# ProPrj_gpsdo-Phil1_2025-08-17.net
KiCad netlist of a schematic drawn in EasyEDA Pro
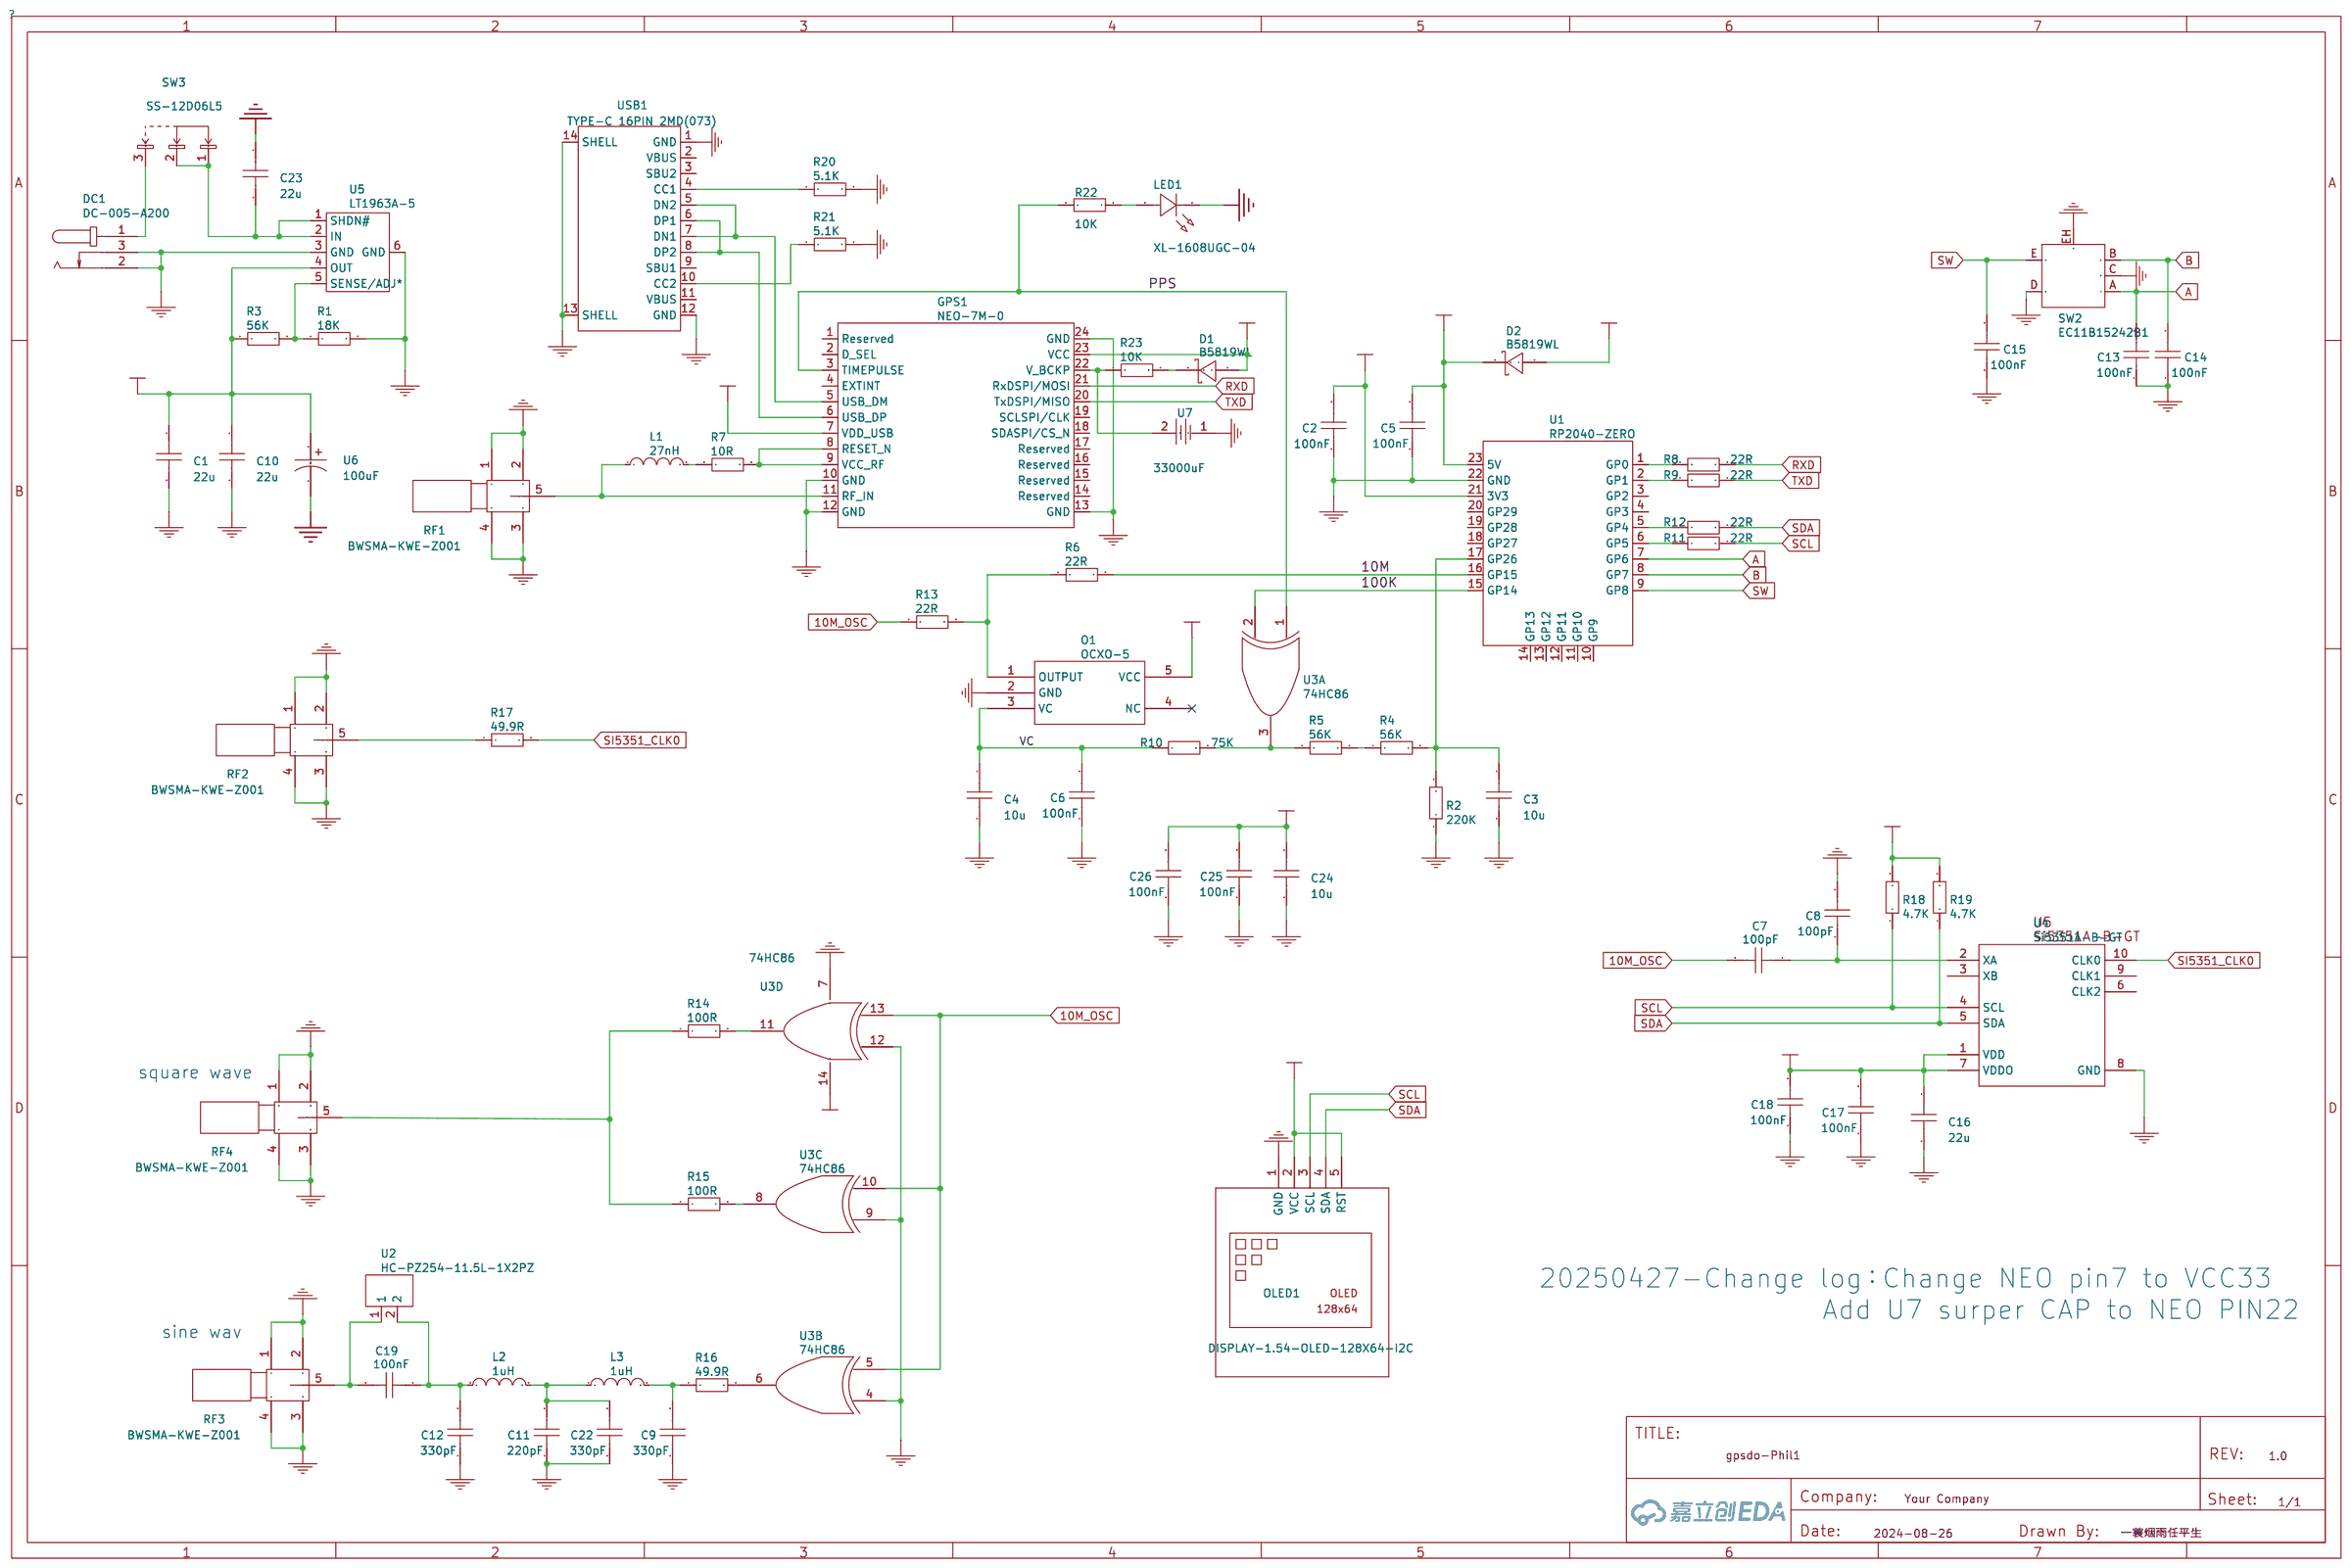
[diagram p0: schematic sheet]

(export (version "E")
  (design (tool "Eeschema 10.0.6"))
  (components
    (comp (ref "C1")
      (value "22u")
      (footprint "easyedapro:C0805")
      (description "容值:100nF;精度:±10%;额定电压:50V;温度系数:X7R;")
      (libsource (lib "easyedapro") (part "C1210X7R475K630NT"))
    )
    (comp (ref "C2")
      (value "100nF")
      (footprint "easyedapro:C0603")
      (fields (field (name "Manufacturer Part") "CC0603KRX7R9BB104") (field (name "Manufacturer") "YAGEO"))
      (libsource (lib "easyedapro") (part "100nF"))
    )
    (comp (ref "C3")
      (value "10u")
      (footprint "easyedapro:C0805")
      (description "容值:100nF;精度:±10%;额定电压:50V;温度系数:X7R;")
      (libsource (lib "easyedapro") (part "C1210X7R475K630NT"))
    )
    (comp (ref "C4")
      (value "10u")
      (footprint "easyedapro:C0805")
      (description "容值:100nF;精度:±10%;额定电压:50V;温度系数:X7R;")
      (libsource (lib "easyedapro") (part "C1210X7R475K630NT"))
    )
    (comp (ref "C5")
      (value "100nF")
      (footprint "easyedapro:C0603")
      (fields (field (name "Manufacturer Part") "CC0603KRX7R9BB104") (field (name "Manufacturer") "YAGEO"))
      (libsource (lib "easyedapro") (part "100nF"))
    )
    (comp (ref "C6")
      (value "100nF")
      (footprint "easyedapro:C0603")
      (fields (field (name "Manufacturer Part") "CC0603KRX7R9BB104") (field (name "Manufacturer") "YAGEO"))
      (libsource (lib "easyedapro") (part "100nF"))
    )
    (comp (ref "C7")
      (value "100pF")
      (footprint "easyedapro:C0603")
      (fields (field (name "Manufacturer Part") "CC0603KRX7R9BB104") (field (name "Manufacturer") "YAGEO"))
      (libsource (lib "easyedapro") (part "100pF"))
    )
    (comp (ref "C8")
      (value "100pF")
      (footprint "easyedapro:C0603")
      (fields (field (name "Manufacturer Part") "CC0603KRX7R9BB104") (field (name "Manufacturer") "YAGEO"))
      (libsource (lib "easyedapro") (part "100pF"))
    )
    (comp (ref "C9")
      (value "330pF")
      (footprint "easyedapro:C0603")
      (fields (field (name "Manufacturer Part") "CC0603KRX7R9BB104") (field (name "Manufacturer") "YAGEO"))
      (libsource (lib "easyedapro") (part "330pF"))
    )
    (comp (ref "C10")
      (value "22u")
      (footprint "easyedapro:C0805")
      (description "容值:100nF;精度:±10%;额定电压:50V;温度系数:X7R;")
      (libsource (lib "easyedapro") (part "C1210X7R475K630NT"))
    )
    (comp (ref "C11")
      (value "220pF")
      (footprint "easyedapro:C0603")
      (fields (field (name "Manufacturer Part") "CC0603KRX7R9BB104") (field (name "Manufacturer") "YAGEO"))
      (libsource (lib "easyedapro") (part "220pF"))
    )
    (comp (ref "C12")
      (value "330pF")
      (footprint "easyedapro:C0603")
      (fields (field (name "Manufacturer Part") "CC0603KRX7R9BB104") (field (name "Manufacturer") "YAGEO"))
      (libsource (lib "easyedapro") (part "330pF"))
    )
    (comp (ref "C13")
      (value "100nF")
      (footprint "easyedapro:C0603")
      (fields (field (name "Manufacturer Part") "CC0603KRX7R9BB104") (field (name "Manufacturer") "YAGEO"))
      (libsource (lib "easyedapro") (part "100nF"))
    )
    (comp (ref "C14")
      (value "100nF")
      (footprint "easyedapro:C0603")
      (fields (field (name "Manufacturer Part") "CC0603KRX7R9BB104") (field (name "Manufacturer") "YAGEO"))
      (libsource (lib "easyedapro") (part "100nF"))
    )
    (comp (ref "C15")
      (value "100nF")
      (footprint "easyedapro:C0603")
      (fields (field (name "Manufacturer Part") "CC0603KRX7R9BB104") (field (name "Manufacturer") "YAGEO"))
      (libsource (lib "easyedapro") (part "100nF"))
    )
    (comp (ref "C16")
      (value "22u")
      (footprint "easyedapro:C0805")
      (description "容值:100nF;精度:±10%;额定电压:50V;温度系数:X7R;")
      (libsource (lib "easyedapro") (part "C1210X7R475K630NT"))
    )
    (comp (ref "C17")
      (value "100nF")
      (footprint "easyedapro:C0603")
      (fields (field (name "Manufacturer Part") "CC0603KRX7R9BB104") (field (name "Manufacturer") "YAGEO"))
      (libsource (lib "easyedapro") (part "100nF"))
    )
    (comp (ref "C18")
      (value "100nF")
      (footprint "easyedapro:C0603")
      (fields (field (name "Manufacturer Part") "CC0603KRX7R9BB104") (field (name "Manufacturer") "YAGEO"))
      (libsource (lib "easyedapro") (part "100nF"))
    )
    (comp (ref "C19")
      (value "100nF")
      (footprint "easyedapro:C0603")
      (fields (field (name "Manufacturer Part") "CC0603KRX7R9BB104") (field (name "Manufacturer") "YAGEO"))
      (libsource (lib "easyedapro") (part "100nF"))
    )
    (comp (ref "C22")
      (value "330pF")
      (footprint "easyedapro:C0603")
      (fields (field (name "Manufacturer Part") "CC0603KRX7R9BB104") (field (name "Manufacturer") "YAGEO"))
      (libsource (lib "easyedapro") (part "330pF"))
    )
    (comp (ref "C23")
      (value "22u")
      (footprint "easyedapro:C0805")
      (description "容值:100nF;精度:±10%;额定电压:50V;温度系数:X7R;")
      (libsource (lib "easyedapro") (part "C1210X7R475K630NT"))
    )
    (comp (ref "C24")
      (value "10u")
      (footprint "easyedapro:C0805")
      (description "容值:100nF;精度:±10%;额定电压:50V;温度系数:X7R;")
      (libsource (lib "easyedapro") (part "C1210X7R475K630NT"))
    )
    (comp (ref "C25")
      (value "100nF")
      (footprint "easyedapro:C0603")
      (fields (field (name "Manufacturer Part") "CC0603KRX7R9BB104") (field (name "Manufacturer") "YAGEO"))
      (libsource (lib "easyedapro") (part "100nF"))
    )
    (comp (ref "C26")
      (value "100nF")
      (footprint "easyedapro:C0603")
      (fields (field (name "Manufacturer Part") "CC0603KRX7R9BB104") (field (name "Manufacturer") "YAGEO"))
      (libsource (lib "easyedapro") (part "100nF"))
    )
    (comp (ref "D1")
      (value "B5819WL")
      (footprint "easyedapro:SOD-123F_L2.8-W1.8-LS3.7-RD")
      (fields (field (name "Manufacturer") "SHIKUES(时科)"))
      (libsource (lib "easyedapro") (part "B5819WL"))
    )
    (comp (ref "D2")
      (value "B5819WL")
      (footprint "easyedapro:SOD-123F_L2.8-W1.8-LS3.7-RD")
      (fields (field (name "Manufacturer") "SHIKUES(时科)"))
      (libsource (lib "easyedapro") (part "B5819WL"))
    )
    (comp (ref "DC1")
      (value "DC-005-A200")
      (footprint "easyedapro:DC-IN-TH_DC-005-A200")
      (fields (field (name "Manufacturer") "XUNPU(讯普)"))
      (libsource (lib "easyedapro") (part "DC-005-A200"))
    )
    (comp (ref "GPS1")
      (value "NEO-7M-0")
      (footprint "easyedapro:GPS-SMD_NEO-7M-0")
      (fields (field (name "Manufacturer") "U-BLOX"))
      (libsource (lib "easyedapro") (part "NEO-7M-0"))
    )
    (comp (ref "L1")
      (value "27nH")
      (footprint "easyedapro:L0603")
      (fields (field (name "Manufacturer") "muRata(村田)"))
      (libsource (lib "easyedapro") (part "27nH"))
    )
    (comp (ref "L2")
      (value "1uH")
      (footprint "easyedapro:IND-SMD_L2.3-W1.7-1")
      (fields (field (name "Manufacturer") "Sunltech(韩国顺磁)"))
      (libsource (lib "easyedapro") (part "1uH"))
    )
    (comp (ref "L3")
      (value "1uH")
      (footprint "easyedapro:IND-SMD_L2.3-W1.7-1")
      (fields (field (name "Manufacturer") "Sunltech(韩国顺磁)"))
      (libsource (lib "easyedapro") (part "1uH"))
    )
    (comp (ref "LED1")
      (value "XL-1608UGC-04")
      (footprint "easyedapro:LED0603-RD_GREEN")
      (fields (field (name "Manufacturer") "XINGLIGHT(成兴光)"))
      (libsource (lib "easyedapro") (part "XL-1608UGC-04"))
    )
    (comp (ref "O1")
      (value "OCXO-5")
      (footprint "easyedapro:OCXO-5")
      (libsource (lib "easyedapro") (part "OCXO-5"))
    )
    (comp (ref "OLED1")
      (value "DISPLAY-1.54-OLED-128X64-I2C")
      (footprint "easyedapro:1.54 I2C OLED SSD1309")
      (libsource (lib "easyedapro") (part "DISPLAY-1.54-OLED-128X64-I2C"))
    )
    (comp (ref "R1")
      (value "18K")
      (footprint "easyedapro:R0603")
      (fields (field (name "Manufacturer Part") "0603WAF1002T5E") (field (name "Manufacturer") "UniOhm"))
      (libsource (lib "easyedapro") (part "2.4K"))
    )
    (comp (ref "R2")
      (value "220K")
      (footprint "easyedapro:R0603")
      (fields (field (name "Manufacturer Part") "0603WAF1002T5E") (field (name "Manufacturer") "UniOhm"))
      (libsource (lib "easyedapro") (part "220K"))
    )
    (comp (ref "R3")
      (value "56K")
      (footprint "easyedapro:R0603")
      (fields (field (name "Manufacturer Part") "0603WAF1002T5E") (field (name "Manufacturer") "UniOhm"))
      (libsource (lib "easyedapro") (part "10K"))
    )
    (comp (ref "R4")
      (value "56K")
      (footprint "easyedapro:R0603")
      (fields (field (name "Manufacturer Part") "0603WAF1002T5E") (field (name "Manufacturer") "UniOhm"))
      (libsource (lib "easyedapro") (part "56K"))
    )
    (comp (ref "R5")
      (value "56K")
      (footprint "easyedapro:R0603")
      (fields (field (name "Manufacturer Part") "0603WAF1002T5E") (field (name "Manufacturer") "UniOhm"))
      (libsource (lib "easyedapro") (part "56K"))
    )
    (comp (ref "R6")
      (value "22R")
      (footprint "easyedapro:R0603")
      (fields (field (name "Manufacturer Part") "0603WAF1002T5E") (field (name "Manufacturer") "UniOhm"))
      (libsource (lib "easyedapro") (part "22R"))
    )
    (comp (ref "R7")
      (value "10R")
      (footprint "easyedapro:R0603")
      (fields (field (name "Manufacturer Part") "0603WAF1002T5E") (field (name "Manufacturer") "UniOhm"))
      (libsource (lib "easyedapro") (part "10R"))
    )
    (comp (ref "R8")
      (value "22R")
      (footprint "easyedapro:R0603")
      (fields (field (name "Manufacturer Part") "0603WAF1002T5E") (field (name "Manufacturer") "UniOhm"))
      (libsource (lib "easyedapro") (part "22R"))
    )
    (comp (ref "R9")
      (value "22R")
      (footprint "easyedapro:R0603")
      (fields (field (name "Manufacturer Part") "0603WAF1002T5E") (field (name "Manufacturer") "UniOhm"))
      (libsource (lib "easyedapro") (part "22R"))
    )
    (comp (ref "R10")
      (value "75K")
      (footprint "easyedapro:R0603")
      (fields (field (name "Manufacturer Part") "0603WAF1002T5E") (field (name "Manufacturer") "UniOhm"))
      (libsource (lib "easyedapro") (part "75K"))
    )
    (comp (ref "R11")
      (value "22R")
      (footprint "easyedapro:R0603")
      (fields (field (name "Manufacturer Part") "0603WAF1002T5E") (field (name "Manufacturer") "UniOhm"))
      (libsource (lib "easyedapro") (part "22R"))
    )
    (comp (ref "R12")
      (value "22R")
      (footprint "easyedapro:R0603")
      (fields (field (name "Manufacturer Part") "0603WAF1002T5E") (field (name "Manufacturer") "UniOhm"))
      (libsource (lib "easyedapro") (part "22R"))
    )
    (comp (ref "R13")
      (value "22R")
      (footprint "easyedapro:R0603")
      (fields (field (name "Manufacturer Part") "0603WAF1002T5E") (field (name "Manufacturer") "UniOhm"))
      (libsource (lib "easyedapro") (part "22R"))
    )
    (comp (ref "R14")
      (value "100R")
      (footprint "easyedapro:R0603")
      (fields (field (name "Manufacturer Part") "0603WAF1002T5E") (field (name "Manufacturer") "UniOhm"))
      (libsource (lib "easyedapro") (part "100R"))
    )
    (comp (ref "R15")
      (value "100R")
      (footprint "easyedapro:R0603")
      (fields (field (name "Manufacturer Part") "0603WAF1002T5E") (field (name "Manufacturer") "UniOhm"))
      (libsource (lib "easyedapro") (part "100R"))
    )
    (comp (ref "R16")
      (value "49.9R")
      (footprint "easyedapro:R0603")
      (fields (field (name "Manufacturer Part") "0603WAF1002T5E") (field (name "Manufacturer") "UniOhm"))
      (libsource (lib "easyedapro") (part "49.9R"))
    )
    (comp (ref "R17")
      (value "49.9R")
      (footprint "easyedapro:R0603")
      (fields (field (name "Manufacturer Part") "0603WAF1002T5E") (field (name "Manufacturer") "UniOhm"))
      (libsource (lib "easyedapro") (part "49.9R"))
    )
    (comp (ref "R18")
      (value "4.7K")
      (footprint "easyedapro:R0603")
      (fields (field (name "Manufacturer Part") "0603WAF1002T5E") (field (name "Manufacturer") "UniOhm"))
      (libsource (lib "easyedapro") (part "4.7K"))
    )
    (comp (ref "R19")
      (value "4.7K")
      (footprint "easyedapro:R0603")
      (fields (field (name "Manufacturer Part") "0603WAF1002T5E") (field (name "Manufacturer") "UniOhm"))
      (libsource (lib "easyedapro") (part "4.7K"))
    )
    (comp (ref "R20")
      (value "5.1K")
      (footprint "easyedapro:R0603")
      (fields (field (name "Manufacturer Part") "0603WAF1002T5E") (field (name "Manufacturer") "UniOhm"))
      (libsource (lib "easyedapro") (part "5.1K"))
    )
    (comp (ref "R21")
      (value "5.1K")
      (footprint "easyedapro:R0603")
      (fields (field (name "Manufacturer Part") "0603WAF1002T5E") (field (name "Manufacturer") "UniOhm"))
      (libsource (lib "easyedapro") (part "5.1K"))
    )
    (comp (ref "R22")
      (value "10K")
      (footprint "easyedapro:R0603")
      (fields (field (name "Manufacturer Part") "0603WAF1002T5E") (field (name "Manufacturer") "UniOhm"))
      (libsource (lib "easyedapro") (part "4.7K"))
    )
    (comp (ref "R23")
      (value "10K")
      (footprint "easyedapro:R0603")
      (fields (field (name "Manufacturer Part") "0603WAF1002T5E") (field (name "Manufacturer") "UniOhm"))
      (libsource (lib "easyedapro") (part "2.4K"))
    )
    (comp (ref "RF1")
      (value "BWSMA-KWE-Z001")
      (footprint "easyedapro:SMA-TH_BWSMA-KWE-Z001")
      (fields (field (name "Manufacturer") "BAT WIRELESS(蝙蝠无线)"))
      (libsource (lib "easyedapro") (part "BWSMA-KWE-Z001"))
    )
    (comp (ref "RF2")
      (value "BWSMA-KWE-Z001")
      (footprint "easyedapro:SMA-TH_BWSMA-KWE-Z001")
      (fields (field (name "Manufacturer") "BAT WIRELESS(蝙蝠无线)"))
      (libsource (lib "easyedapro") (part "BWSMA-KWE-Z001"))
    )
    (comp (ref "RF3")
      (value "BWSMA-KWE-Z001")
      (footprint "easyedapro:SMA-TH_BWSMA-KWE-Z001")
      (fields (field (name "Manufacturer") "BAT WIRELESS(蝙蝠无线)"))
      (libsource (lib "easyedapro") (part "BWSMA-KWE-Z001"))
    )
    (comp (ref "RF4")
      (value "BWSMA-KWE-Z001")
      (footprint "easyedapro:SMA-TH_BWSMA-KWE-Z001")
      (fields (field (name "Manufacturer") "BAT WIRELESS(蝙蝠无线)"))
      (libsource (lib "easyedapro") (part "BWSMA-KWE-Z001"))
    )
    (comp (ref "SW2")
      (value "EC11B15242B1")
      (footprint "easyedapro:SW-TH_EC11B1524XX")
      (fields (field (name "Manufacturer") "ALPSALPINE(阿尔卑斯阿尔派)"))
      (libsource (lib "easyedapro") (part "EC11B15242B1"))
    )
    (comp (ref "SW3")
      (value "SS-12D06L5")
      (footprint "easyedapro:SW-TH_3P-P4.70_L11.1-W12.7")
      (description "电路结构:单刀双掷;安装方式:侧插;开关颜色:黑色;额定电流(DC):3A;额定电压(DC):250V;额定电流(AC):3A;额定电压(AC):250V;机械寿命:1万次;")
      (fields (field (name "Manufacturer") "XKB Connectivity(中国星坤)"))
      (libsource (lib "easyedapro") (part "SS-12D06L5"))
    )
    (comp (ref "U1")
      (value "RP2040-ZERO")
      (footprint "easyedapro:COMM-SMD_RP2040-ZERO")
      (fields (field (name "Manufacturer") "Waveshare(微雪电子)"))
      (libsource (lib "easyedapro") (part "RP2040-ZERO"))
    )
    (comp (ref "U2")
      (value "HC-PZ254-11.5L-1X2PZ")
      (footprint "easyedapro:CONN-TH_HC-PZ254-11.5L-1X2PZ")
      (fields
        (field (name "Manufacturer Part") "HC-PZ254-11.5L-1x2PZ")
        (field (name "Manufacturer") "HC(虹成电子)")
      )
      (libsource (lib "easyedapro") (part "HC-PZ254-11.5L-1X2PZ"))
    )
    (comp (ref "U3")
      (value "74HC86")
      (footprint "easyedapro:SOP-14")
      (libsource (lib "easyedapro") (part "74HC86"))
    )
    (comp (ref "U4")
      (value "Si5351A-B-GT")
      (footprint "easyedapro:SI5351A-B-GT-MSOP-10_L3.0-W3.0-P0.50-LS5.0-BL")
      (libsource (lib "easyedapro") (part "Si5351A-B-GT"))
    )
    (comp (ref "U5")
      (value "LT1963A-5")
      (footprint "easyedapro:DD-PAK-5_L10.6-W10.3-P1.70-LS14.5-BR")
      (fields
        (field (name "Manufacturer Part") "LT1963AEQ-1.8#PBF")
        (field (name "Manufacturer") "Analog Devices")
      )
      (libsource (lib "easyedapro") (part "LT1963A-5"))
    )
    (comp (ref "U6")
      (value "100uF")
      (footprint "easyedapro:CAP-SMD_BD6.3-L6.6-W6.6-LS7.3-FD")
      (description "容值:100uF;精度:±20%;额定电压:25V;")
      (fields (field (name "Manufacturer Part") "118EC221") (field (name "Manufacturer") "KNSCHA(科尼盛)"))
      (libsource (lib "easyedapro") (part "118EC221"))
    )
    (comp (ref "U7")
      (value "33000uF")
      (footprint "easyedapro:BAT-SMD_SM3R3333-T01")
      (description "容值:33000uF;精度:-20%~+80%;额定电压:3.3V;漏电流:100uA@30mins;等效串联电阻:200Ω@1kHz;")
      (fields (field (name "Manufacturer Part") "SM3R3333 T01") (field (name "Manufacturer") "KORCHIP(高奇普)"))
      (libsource (lib "easyedapro") (part "SM3R3333 T01"))
    )
    (comp (ref "USB1")
      (value "TYPE-C 16PIN 2MD(073)")
      (footprint "easyedapro:USB-C-SMD_TYPE-C-6PIN-2MD-073")
      (fields (field (name "Manufacturer") "SHOU HAN(首韩)"))
      (libsource (lib "easyedapro") (part "TYPE-C 16PIN 2MD(073)"))
    )
  )
  (nets
    (net (code "1") (name "+5V") (class "Default")
      (node (ref "C1") (pin "1") (pinfunction "1_1") (pintype "input"))
      (node (ref "C10") (pin "1") (pinfunction "1_1") (pintype "input"))
      (node (ref "C24") (pin "1") (pinfunction "1_1") (pintype "input"))
      (node (ref "C25") (pin "2") (pinfunction "2_2") (pintype "unspecified"))
      (node (ref "C26") (pin "2") (pinfunction "2_2") (pintype "unspecified"))
      (node (ref "D2") (pin "2") (pinfunction "A_2") (pintype "unspecified"))
      (node (ref "O1") (pin "5") (pinfunction "VCC_5") (pintype "unspecified"))
      (node (ref "R3") (pin "1") (pinfunction "1_1") (pintype "input"))
      (node (ref "U3") (pin "14") (pinfunction "14_14") (pintype "unspecified"))
      (node (ref "U5") (pin "4") (pinfunction "OUT_4") (pintype "unspecified"))
      (node (ref "U6") (pin "1") (pinfunction "1_1") (pintype "unspecified"))
    )
    (net (code "2") (name "+5V_PICO") (class "Default")
      (node (ref "C5") (pin "2") (pinfunction "2_2") (pintype "unspecified"))
      (node (ref "D2") (pin "1") (pinfunction "K_1") (pintype "unspecified"))
      (node (ref "U1") (pin "23") (pinfunction "5V_23") (pintype "unspecified"))
    )
    (net (code "3") (name "/10M") (class "Default")
      (node (ref "R6") (pin "2") (pinfunction "2_2") (pintype "input"))
      (node (ref "U1") (pin "16") (pinfunction "GP15_16") (pintype "unspecified"))
    )
    (net (code "4") (name "/100K") (class "Default")
      (node (ref "U1") (pin "15") (pinfunction "GP14_15") (pintype "unspecified"))
      (node (ref "U3") (pin "2") (pintype "unspecified"))
    )
    (net (code "5") (name "/PPS") (class "Default")
      (node (ref "GPS1") (pin "3") (pinfunction "TIMEPULSE_3") (pintype "unspecified"))
      (node (ref "R22") (pin "2") (pinfunction "2_2") (pintype "input"))
      (node (ref "U3") (pin "1") (pintype "unspecified"))
    )
    (net (code "6") (name "/VC") (class "Default")
      (node (ref "C4") (pin "1") (pinfunction "1_1") (pintype "input"))
      (node (ref "C6") (pin "2") (pinfunction "2_2") (pintype "unspecified"))
      (node (ref "O1") (pin "3") (pinfunction "VC_3") (pintype "unspecified"))
      (node (ref "R10") (pin "1") (pinfunction "1_1") (pintype "input"))
    )
    (net (code "7") (name "10M_OSC") (class "Default")
      (node (ref "C7") (pin "2") (pinfunction "2_2") (pintype "unspecified"))
      (node (ref "R13") (pin "1") (pinfunction "1_1") (pintype "input"))
      (node (ref "U3") (pin "10") (pintype "unspecified"))
      (node (ref "U3") (pin "13") (pintype "unspecified"))
      (node (ref "U3") (pin "5") (pintype "unspecified"))
    )
    (net (code "8") (name "A") (class "Default")
      (node (ref "C13") (pin "2") (pinfunction "2_2") (pintype "unspecified"))
      (node (ref "SW2") (pin "A") (pinfunction "A_A") (pintype "unspecified"))
      (node (ref "U1") (pin "7") (pinfunction "GP6_7") (pintype "unspecified"))
    )
    (net (code "9") (name "B") (class "Default")
      (node (ref "C14") (pin "2") (pinfunction "2_2") (pintype "unspecified"))
      (node (ref "SW2") (pin "B") (pinfunction "B_B") (pintype "unspecified"))
      (node (ref "U1") (pin "8") (pinfunction "GP7_8") (pintype "unspecified"))
    )
    (net (code "10") (name "GND") (class "Default")
      (node (ref "C1") (pin "2") (pinfunction "2_2") (pintype "input"))
      (node (ref "C10") (pin "2") (pinfunction "2_2") (pintype "input"))
      (node (ref "C11") (pin "1") (pinfunction "1_1") (pintype "unspecified"))
      (node (ref "C12") (pin "1") (pinfunction "1_1") (pintype "unspecified"))
      (node (ref "C13") (pin "1") (pinfunction "1_1") (pintype "unspecified"))
      (node (ref "C14") (pin "1") (pinfunction "1_1") (pintype "unspecified"))
      (node (ref "C15") (pin "1") (pinfunction "1_1") (pintype "unspecified"))
      (node (ref "C16") (pin "2") (pinfunction "2_2") (pintype "input"))
      (node (ref "C17") (pin "1") (pinfunction "1_1") (pintype "unspecified"))
      (node (ref "C18") (pin "1") (pinfunction "1_1") (pintype "unspecified"))
      (node (ref "C2") (pin "1") (pinfunction "1_1") (pintype "unspecified"))
      (node (ref "C22") (pin "1") (pinfunction "1_1") (pintype "unspecified"))
      (node (ref "C23") (pin "1") (pinfunction "1_1") (pintype "input"))
      (node (ref "C24") (pin "2") (pinfunction "2_2") (pintype "input"))
      (node (ref "C25") (pin "1") (pinfunction "1_1") (pintype "unspecified"))
      (node (ref "C26") (pin "1") (pinfunction "1_1") (pintype "unspecified"))
      (node (ref "C3") (pin "2") (pinfunction "2_2") (pintype "input"))
      (node (ref "C4") (pin "2") (pinfunction "2_2") (pintype "input"))
      (node (ref "C5") (pin "1") (pinfunction "1_1") (pintype "unspecified"))
      (node (ref "C6") (pin "1") (pinfunction "1_1") (pintype "unspecified"))
      (node (ref "C8") (pin "2") (pinfunction "2_2") (pintype "unspecified"))
      (node (ref "C9") (pin "1") (pinfunction "1_1") (pintype "unspecified"))
      (node (ref "DC1") (pin "2") (pinfunction "2_2") (pintype "unspecified"))
      (node (ref "DC1") (pin "3") (pinfunction "3_3") (pintype "unspecified"))
      (node (ref "GPS1") (pin "10") (pinfunction "GND_10") (pintype "unspecified"))
      (node (ref "GPS1") (pin "12") (pinfunction "GND_12") (pintype "unspecified"))
      (node (ref "GPS1") (pin "13") (pinfunction "GND_13") (pintype "unspecified"))
      (node (ref "GPS1") (pin "24") (pinfunction "GND_24") (pintype "unspecified"))
      (node (ref "LED1") (pin "1") (pinfunction "K_1") (pintype "unspecified"))
      (node (ref "O1") (pin "2") (pinfunction "GND_2") (pintype "unspecified"))
      (node (ref "OLED1") (pin "1") (pinfunction "GND_1") (pintype "unspecified"))
      (node (ref "R1") (pin "2") (pinfunction "2_2") (pintype "input"))
      (node (ref "R2") (pin "1") (pinfunction "1_1") (pintype "input"))
      (node (ref "R20") (pin "2") (pinfunction "2_2") (pintype "input"))
      (node (ref "R21") (pin "2") (pinfunction "2_2") (pintype "input"))
      (node (ref "RF1") (pin "1") (pinfunction "1_1") (pintype "unspecified"))
      (node (ref "RF1") (pin "2") (pinfunction "2_2") (pintype "unspecified"))
      (node (ref "RF1") (pin "3") (pinfunction "3_3") (pintype "unspecified"))
      (node (ref "RF1") (pin "4") (pinfunction "4_4") (pintype "unspecified"))
      (node (ref "RF2") (pin "1") (pinfunction "1_1") (pintype "unspecified"))
      (node (ref "RF2") (pin "2") (pinfunction "2_2") (pintype "unspecified"))
      (node (ref "RF2") (pin "3") (pinfunction "3_3") (pintype "unspecified"))
      (node (ref "RF2") (pin "4") (pinfunction "4_4") (pintype "unspecified"))
      (node (ref "RF3") (pin "1") (pinfunction "1_1") (pintype "unspecified"))
      (node (ref "RF3") (pin "2") (pinfunction "2_2") (pintype "unspecified"))
      (node (ref "RF3") (pin "3") (pinfunction "3_3") (pintype "unspecified"))
      (node (ref "RF3") (pin "4") (pinfunction "4_4") (pintype "unspecified"))
      (node (ref "RF4") (pin "1") (pinfunction "1_1") (pintype "unspecified"))
      (node (ref "RF4") (pin "2") (pinfunction "2_2") (pintype "unspecified"))
      (node (ref "RF4") (pin "3") (pinfunction "3_3") (pintype "unspecified"))
      (node (ref "RF4") (pin "4") (pinfunction "4_4") (pintype "unspecified"))
      (node (ref "SW2") (pin "C") (pinfunction "C_C") (pintype "unspecified"))
      (node (ref "SW2") (pin "D") (pinfunction "D_D") (pintype "unspecified"))
      (node (ref "SW2") (pin "EH") (pinfunction "EH_EH") (pintype "unspecified"))
      (node (ref "U1") (pin "22") (pinfunction "GND_22") (pintype "unspecified"))
      (node (ref "U3") (pin "12") (pintype "unspecified"))
      (node (ref "U3") (pin "4") (pintype "unspecified"))
      (node (ref "U3") (pin "7") (pinfunction "7_7") (pintype "unspecified"))
      (node (ref "U3") (pin "9") (pintype "unspecified"))
      (node (ref "U4") (pin "8") (pinfunction "GND_8") (pintype "unspecified"))
      (node (ref "U5") (pin "3") (pinfunction "GND_3") (pintype "unspecified"))
      (node (ref "U5") (pin "6") (pinfunction "GND_6") (pintype "unspecified"))
      (node (ref "U6") (pin "2") (pinfunction "2_2") (pintype "unspecified"))
      (node (ref "U7") (pin "1") (pinfunction "1_1") (pintype "input"))
      (node (ref "USB1") (pin "1") (pinfunction "GND_1") (pintype "unspecified"))
      (node (ref "USB1") (pin "12") (pinfunction "GND_12") (pintype "unspecified"))
      (node (ref "USB1") (pin "13") (pinfunction "SHELL_13") (pintype "unspecified"))
      (node (ref "USB1") (pin "14") (pinfunction "SHELL_14") (pintype "unspecified"))
    )
    (net (code "11") (name "Net-(C9-Pad2)") (class "Default")
      (node (ref "C9") (pin "2") (pinfunction "2_2") (pintype "unspecified"))
      (node (ref "L3") (pin "2") (pinfunction "2_2") (pintype "unspecified"))
      (node (ref "R16") (pin "1") (pinfunction "1_1") (pintype "input"))
    )
    (net (code "12") (name "Net-(C11-Pad2)") (class "Default")
      (node (ref "C11") (pin "2") (pinfunction "2_2") (pintype "unspecified"))
      (node (ref "C22") (pin "2") (pinfunction "2_2") (pintype "unspecified"))
      (node (ref "L2") (pin "2") (pinfunction "2_2") (pintype "unspecified"))
      (node (ref "L3") (pin "1") (pinfunction "1_1") (pintype "unspecified"))
    )
    (net (code "13") (name "Net-(C12-Pad2)") (class "Default")
      (node (ref "C12") (pin "2") (pinfunction "2_2") (pintype "unspecified"))
      (node (ref "C19") (pin "1") (pinfunction "1_1") (pintype "unspecified"))
      (node (ref "L2") (pin "1") (pinfunction "1_1") (pintype "unspecified"))
      (node (ref "U2") (pin "2") (pinfunction "2_2") (pintype "unspecified"))
    )
    (net (code "14") (name "Net-(C19-Pad2)") (class "Default")
      (node (ref "C19") (pin "2") (pinfunction "2_2") (pintype "unspecified"))
      (node (ref "RF3") (pin "5") (pinfunction "5_5") (pintype "unspecified"))
      (node (ref "U2") (pin "1") (pinfunction "1_1") (pintype "unspecified"))
    )
    (net (code "15") (name "Net-(D1-K)") (class "Default")
      (node (ref "D1") (pin "1") (pinfunction "K_1") (pintype "unspecified"))
      (node (ref "R23") (pin "2") (pinfunction "2_2") (pintype "input"))
    )
    (net (code "16") (name "Net-(DC1-Pad1)") (class "Default")
      (node (ref "DC1") (pin "1") (pinfunction "1_1") (pintype "unspecified"))
      (node (ref "SW3") (pin "3") (pinfunction "3_3") (pintype "unspecified"))
    )
    (net (code "17") (name "Net-(GPS1-RESET_N)") (class "Default")
      (node (ref "GPS1") (pin "8") (pinfunction "RESET_N_8") (pintype "unspecified"))
      (node (ref "GPS1") (pin "9") (pinfunction "VCC_RF_9") (pintype "unspecified"))
      (node (ref "R7") (pin "2") (pinfunction "2_2") (pintype "input"))
    )
    (net (code "18") (name "Net-(GPS1-RF_IN)") (class "Default")
      (node (ref "GPS1") (pin "11") (pinfunction "RF_IN_11") (pintype "unspecified"))
      (node (ref "L1") (pin "1") (pinfunction "1_1") (pintype "unspecified"))
      (node (ref "RF1") (pin "5") (pinfunction "5_5") (pintype "unspecified"))
    )
    (net (code "19") (name "Net-(GPS1-USB_DM)") (class "Default")
      (node (ref "GPS1") (pin "5") (pinfunction "USB_DM_5") (pintype "unspecified"))
      (node (ref "USB1") (pin "5") (pinfunction "DN2_5") (pintype "unspecified"))
      (node (ref "USB1") (pin "7") (pinfunction "DN1_7") (pintype "unspecified"))
    )
    (net (code "20") (name "Net-(GPS1-USB_DP)") (class "Default")
      (node (ref "GPS1") (pin "6") (pinfunction "USB_DP_6") (pintype "unspecified"))
      (node (ref "USB1") (pin "6") (pinfunction "DP1_6") (pintype "unspecified"))
      (node (ref "USB1") (pin "8") (pinfunction "DP2_8") (pintype "unspecified"))
    )
    (net (code "21") (name "Net-(GPS1-V_BCKP)") (class "Default")
      (node (ref "GPS1") (pin "22") (pinfunction "V_BCKP_22") (pintype "unspecified"))
      (node (ref "R23") (pin "1") (pinfunction "1_1") (pintype "input"))
      (node (ref "U7") (pin "2") (pinfunction "2_2") (pintype "input"))
    )
    (net (code "22") (name "Net-(L1-Pad2)") (class "Default")
      (node (ref "L1") (pin "2") (pinfunction "2_2") (pintype "unspecified"))
      (node (ref "R7") (pin "1") (pinfunction "1_1") (pintype "input"))
    )
    (net (code "23") (name "Net-(LED1-A)") (class "Default")
      (node (ref "LED1") (pin "2") (pinfunction "A_2") (pintype "unspecified"))
      (node (ref "R22") (pin "1") (pinfunction "1_1") (pintype "input"))
    )
    (net (code "24") (name "Net-(O1-OUTPUT)") (class "Default")
      (node (ref "O1") (pin "1") (pinfunction "OUTPUT_1") (pintype "unspecified"))
      (node (ref "R13") (pin "2") (pinfunction "2_2") (pintype "input"))
      (node (ref "R6") (pin "1") (pinfunction "1_1") (pintype "input"))
    )
    (net (code "25") (name "Net-(R4-Pad1)") (class "Default")
      (node (ref "R4") (pin "1") (pinfunction "1_1") (pintype "input"))
      (node (ref "R5") (pin "2") (pinfunction "2_2") (pintype "input"))
    )
    (net (code "26") (name "Net-(R10-Pad2)") (class "Default")
      (node (ref "R10") (pin "2") (pinfunction "2_2") (pintype "input"))
      (node (ref "R5") (pin "1") (pinfunction "1_1") (pintype "input"))
      (node (ref "U3") (pin "3") (pintype "unspecified"))
    )
    (net (code "27") (name "Net-(R14-Pad1)") (class "Default")
      (node (ref "R14") (pin "1") (pinfunction "1_1") (pintype "input"))
      (node (ref "R15") (pin "1") (pinfunction "1_1") (pintype "input"))
      (node (ref "RF4") (pin "5") (pinfunction "5_5") (pintype "unspecified"))
    )
    (net (code "28") (name "Net-(R14-Pad2)") (class "Default")
      (node (ref "R14") (pin "2") (pinfunction "2_2") (pintype "input"))
      (node (ref "U3") (pin "11") (pintype "unspecified"))
    )
    (net (code "29") (name "Net-(R15-Pad2)") (class "Default")
      (node (ref "R15") (pin "2") (pinfunction "2_2") (pintype "input"))
      (node (ref "U3") (pin "8") (pintype "unspecified"))
    )
    (net (code "30") (name "Net-(R16-Pad2)") (class "Default")
      (node (ref "R16") (pin "2") (pinfunction "2_2") (pintype "input"))
      (node (ref "U3") (pin "6") (pintype "unspecified"))
    )
    (net (code "31") (name "Net-(R17-Pad1)") (class "Default")
      (node (ref "R17") (pin "1") (pinfunction "1_1") (pintype "input"))
      (node (ref "RF2") (pin "5") (pinfunction "5_5") (pintype "unspecified"))
    )
    (net (code "32") (name "Net-(U1-GP0)") (class "Default")
      (node (ref "R8") (pin "1") (pinfunction "1_1") (pintype "input"))
      (node (ref "U1") (pin "1") (pinfunction "GP0_1") (pintype "unspecified"))
    )
    (net (code "33") (name "Net-(U1-GP1)") (class "Default")
      (node (ref "R9") (pin "1") (pinfunction "1_1") (pintype "input"))
      (node (ref "U1") (pin "2") (pinfunction "GP1_2") (pintype "unspecified"))
    )
    (net (code "34") (name "Net-(U1-GP4)") (class "Default")
      (node (ref "R12") (pin "1") (pinfunction "1_1") (pintype "input"))
      (node (ref "U1") (pin "5") (pinfunction "GP4_5") (pintype "unspecified"))
    )
    (net (code "35") (name "Net-(U1-GP5)") (class "Default")
      (node (ref "R11") (pin "1") (pinfunction "1_1") (pintype "input"))
      (node (ref "U1") (pin "6") (pinfunction "GP5_6") (pintype "unspecified"))
    )
    (net (code "36") (name "Net-(U1-GP26)") (class "Default")
      (node (ref "C3") (pin "1") (pinfunction "1_1") (pintype "input"))
      (node (ref "R2") (pin "2") (pinfunction "2_2") (pintype "input"))
      (node (ref "R4") (pin "2") (pinfunction "2_2") (pintype "input"))
      (node (ref "U1") (pin "17") (pinfunction "GP26_17") (pintype "unspecified"))
    )
    (net (code "37") (name "Net-(U4-XA)") (class "Default")
      (node (ref "C7") (pin "1") (pinfunction "1_1") (pintype "unspecified"))
      (node (ref "C8") (pin "1") (pinfunction "1_1") (pintype "unspecified"))
      (node (ref "U4") (pin "2") (pinfunction "XA_2") (pintype "unspecified"))
    )
    (net (code "38") (name "Net-(U5-IN)") (class "Default")
      (node (ref "C23") (pin "2") (pinfunction "2_2") (pintype "input"))
      (node (ref "SW3") (pin "1") (pinfunction "1_1") (pintype "unspecified"))
      (node (ref "SW3") (pin "2") (pinfunction "2_2") (pintype "unspecified"))
      (node (ref "U5") (pin "1") (pinfunction "SHDN#_1") (pintype "unspecified"))
      (node (ref "U5") (pin "2") (pinfunction "IN_2") (pintype "unspecified"))
    )
    (net (code "39") (name "Net-(U5-SENSE{slash}ADJ*)") (class "Default")
      (node (ref "R1") (pin "1") (pinfunction "1_1") (pintype "input"))
      (node (ref "R3") (pin "2") (pinfunction "2_2") (pintype "input"))
      (node (ref "U5") (pin "5") (pinfunction "SENSE/ADJ*_5") (pintype "unspecified"))
    )
    (net (code "40") (name "Net-(USB1-CC1)") (class "Default")
      (node (ref "R20") (pin "1") (pinfunction "1_1") (pintype "input"))
      (node (ref "USB1") (pin "4") (pinfunction "CC1_4") (pintype "unspecified"))
    )
    (net (code "41") (name "Net-(USB1-CC2)") (class "Default")
      (node (ref "R21") (pin "1") (pinfunction "1_1") (pintype "input"))
      (node (ref "USB1") (pin "10") (pinfunction "CC2_10") (pintype "unspecified"))
    )
    (net (code "42") (name "RXD") (class "Default")
      (node (ref "GPS1") (pin "21") (pinfunction "RxDSPI/MOSI_21") (pintype "unspecified"))
      (node (ref "R8") (pin "2") (pinfunction "2_2") (pintype "input"))
    )
    (net (code "43") (name "SCL") (class "Default")
      (node (ref "OLED1") (pin "3") (pinfunction "SCL_3") (pintype "unspecified"))
      (node (ref "R11") (pin "2") (pinfunction "2_2") (pintype "input"))
      (node (ref "R18") (pin "1") (pinfunction "1_1") (pintype "input"))
      (node (ref "U4") (pin "4") (pinfunction "SCL_4") (pintype "unspecified"))
    )
    (net (code "44") (name "SDA") (class "Default")
      (node (ref "OLED1") (pin "4") (pinfunction "SDA_4") (pintype "unspecified"))
      (node (ref "R12") (pin "2") (pinfunction "2_2") (pintype "input"))
      (node (ref "R19") (pin "1") (pinfunction "1_1") (pintype "input"))
      (node (ref "U4") (pin "5") (pinfunction "SDA_5") (pintype "unspecified"))
    )
    (net (code "45") (name "SI5351_CLK0") (class "Default")
      (node (ref "R17") (pin "2") (pinfunction "2_2") (pintype "input"))
      (node (ref "U4") (pin "10") (pinfunction "CLK0_10") (pintype "unspecified"))
    )
    (net (code "46") (name "SW") (class "Default")
      (node (ref "C15") (pin "2") (pinfunction "2_2") (pintype "unspecified"))
      (node (ref "SW2") (pin "E") (pinfunction "E_E") (pintype "unspecified"))
      (node (ref "U1") (pin "9") (pinfunction "GP8_9") (pintype "unspecified"))
    )
    (net (code "47") (name "TXD") (class "Default")
      (node (ref "GPS1") (pin "20") (pinfunction "TxDSPI/MISO_20") (pintype "unspecified"))
      (node (ref "R9") (pin "2") (pinfunction "2_2") (pintype "input"))
    )
    (net (code "48") (name "VCC33") (class "Default")
      (node (ref "C16") (pin "1") (pinfunction "1_1") (pintype "input"))
      (node (ref "C17") (pin "2") (pinfunction "2_2") (pintype "unspecified"))
      (node (ref "C18") (pin "2") (pinfunction "2_2") (pintype "unspecified"))
      (node (ref "C2") (pin "2") (pinfunction "2_2") (pintype "unspecified"))
      (node (ref "D1") (pin "2") (pinfunction "A_2") (pintype "unspecified"))
      (node (ref "GPS1") (pin "23") (pinfunction "VCC_23") (pintype "unspecified"))
      (node (ref "GPS1") (pin "7") (pinfunction "VDD_USB_7") (pintype "unspecified"))
      (node (ref "OLED1") (pin "2") (pinfunction "VCC_2") (pintype "unspecified"))
      (node (ref "OLED1") (pin "5") (pinfunction "RST_5") (pintype "unspecified"))
      (node (ref "R18") (pin "2") (pinfunction "2_2") (pintype "input"))
      (node (ref "R19") (pin "2") (pinfunction "2_2") (pintype "input"))
      (node (ref "U1") (pin "21") (pinfunction "3V3_21") (pintype "unspecified"))
      (node (ref "U4") (pin "1") (pinfunction "VDD_1") (pintype "unspecified"))
      (node (ref "U4") (pin "7") (pinfunction "VDDO_7") (pintype "unspecified"))
    )
    (net (code "49") (name "unconnected-(GPS1-D_SEL-Pad2)") (class "Default")
      (node (ref "GPS1") (pin "2") (pinfunction "D_SEL_2") (pintype "unspecified"))
    )
    (net (code "50") (name "unconnected-(GPS1-EXTINT-Pad4)") (class "Default")
      (node (ref "GPS1") (pin "4") (pinfunction "EXTINT_4") (pintype "unspecified"))
    )
    (net (code "51") (name "unconnected-(GPS1-Reserved-Pad1)") (class "Default")
      (node (ref "GPS1") (pin "1") (pinfunction "Reserved_1") (pintype "unspecified"))
    )
    (net (code "52") (name "unconnected-(GPS1-Reserved-Pad14)") (class "Default")
      (node (ref "GPS1") (pin "14") (pinfunction "Reserved_14") (pintype "unspecified"))
    )
    (net (code "53") (name "unconnected-(GPS1-Reserved-Pad15)") (class "Default")
      (node (ref "GPS1") (pin "15") (pinfunction "Reserved_15") (pintype "unspecified"))
    )
    (net (code "54") (name "unconnected-(GPS1-Reserved-Pad16)") (class "Default")
      (node (ref "GPS1") (pin "16") (pinfunction "Reserved_16") (pintype "unspecified"))
    )
    (net (code "55") (name "unconnected-(GPS1-Reserved-Pad17)") (class "Default")
      (node (ref "GPS1") (pin "17") (pinfunction "Reserved_17") (pintype "unspecified"))
    )
    (net (code "56") (name "unconnected-(GPS1-SCLSPI{slash}CLK-Pad19)") (class "Default")
      (node (ref "GPS1") (pin "19") (pinfunction "SCLSPI/CLK_19") (pintype "unspecified"))
    )
    (net (code "57") (name "unconnected-(GPS1-SDASPI{slash}CS_N-Pad18)") (class "Default")
      (node (ref "GPS1") (pin "18") (pinfunction "SDASPI/CS_N_18") (pintype "unspecified"))
    )
    (net (code "58") (name "unconnected-(O1-NC-Pad4)") (class "Default")
      (node (ref "O1") (pin "4") (pinfunction "NC_4") (pintype "unspecified+no_connect"))
    )
    (net (code "59") (name "unconnected-(U1-GP2-Pad3)") (class "Default")
      (node (ref "U1") (pin "3") (pinfunction "GP2_3") (pintype "unspecified"))
    )
    (net (code "60") (name "unconnected-(U1-GP3-Pad4)") (class "Default")
      (node (ref "U1") (pin "4") (pinfunction "GP3_4") (pintype "unspecified"))
    )
    (net (code "61") (name "unconnected-(U1-GP9-Pad10)") (class "Default")
      (node (ref "U1") (pin "10") (pinfunction "GP9_10") (pintype "unspecified"))
    )
    (net (code "62") (name "unconnected-(U1-GP10-Pad11)") (class "Default")
      (node (ref "U1") (pin "11") (pinfunction "GP10_11") (pintype "unspecified"))
    )
    (net (code "63") (name "unconnected-(U1-GP11-Pad12)") (class "Default")
      (node (ref "U1") (pin "12") (pinfunction "GP11_12") (pintype "unspecified"))
    )
    (net (code "64") (name "unconnected-(U1-GP12-Pad13)") (class "Default")
      (node (ref "U1") (pin "13") (pinfunction "GP12_13") (pintype "unspecified"))
    )
    (net (code "65") (name "unconnected-(U1-GP13-Pad14)") (class "Default")
      (node (ref "U1") (pin "14") (pinfunction "GP13_14") (pintype "unspecified"))
    )
    (net (code "66") (name "unconnected-(U1-GP27-Pad18)") (class "Default")
      (node (ref "U1") (pin "18") (pinfunction "GP27_18") (pintype "unspecified"))
    )
    (net (code "67") (name "unconnected-(U1-GP28-Pad19)") (class "Default")
      (node (ref "U1") (pin "19") (pinfunction "GP28_19") (pintype "unspecified"))
    )
    (net (code "68") (name "unconnected-(U1-GP29-Pad20)") (class "Default")
      (node (ref "U1") (pin "20") (pinfunction "GP29_20") (pintype "unspecified"))
    )
    (net (code "69") (name "unconnected-(U4-CLK1-Pad9)") (class "Default")
      (node (ref "U4") (pin "9") (pinfunction "CLK1_9") (pintype "unspecified"))
    )
    (net (code "70") (name "unconnected-(U4-CLK2-Pad6)") (class "Default")
      (node (ref "U4") (pin "6") (pinfunction "CLK2_6") (pintype "unspecified"))
    )
    (net (code "71") (name "unconnected-(U4-XB-Pad3)") (class "Default")
      (node (ref "U4") (pin "3") (pinfunction "XB_3") (pintype "unspecified"))
    )
    (net (code "72") (name "unconnected-(USB1-SBU1-Pad9)") (class "Default")
      (node (ref "USB1") (pin "9") (pinfunction "SBU1_9") (pintype "unspecified"))
    )
    (net (code "73") (name "unconnected-(USB1-SBU2-Pad3)") (class "Default")
      (node (ref "USB1") (pin "3") (pinfunction "SBU2_3") (pintype "unspecified"))
    )
    (net (code "74") (name "unconnected-(USB1-VBUS-Pad2)") (class "Default")
      (node (ref "USB1") (pin "2") (pinfunction "VBUS_2") (pintype "unspecified"))
    )
    (net (code "75") (name "unconnected-(USB1-VBUS-Pad11)") (class "Default")
      (node (ref "USB1") (pin "11") (pinfunction "VBUS_11") (pintype "unspecified"))
    )
  )
)
